# TrinketBlinkM0K.net
KiCad netlist of a schematic drawn in EAGLE
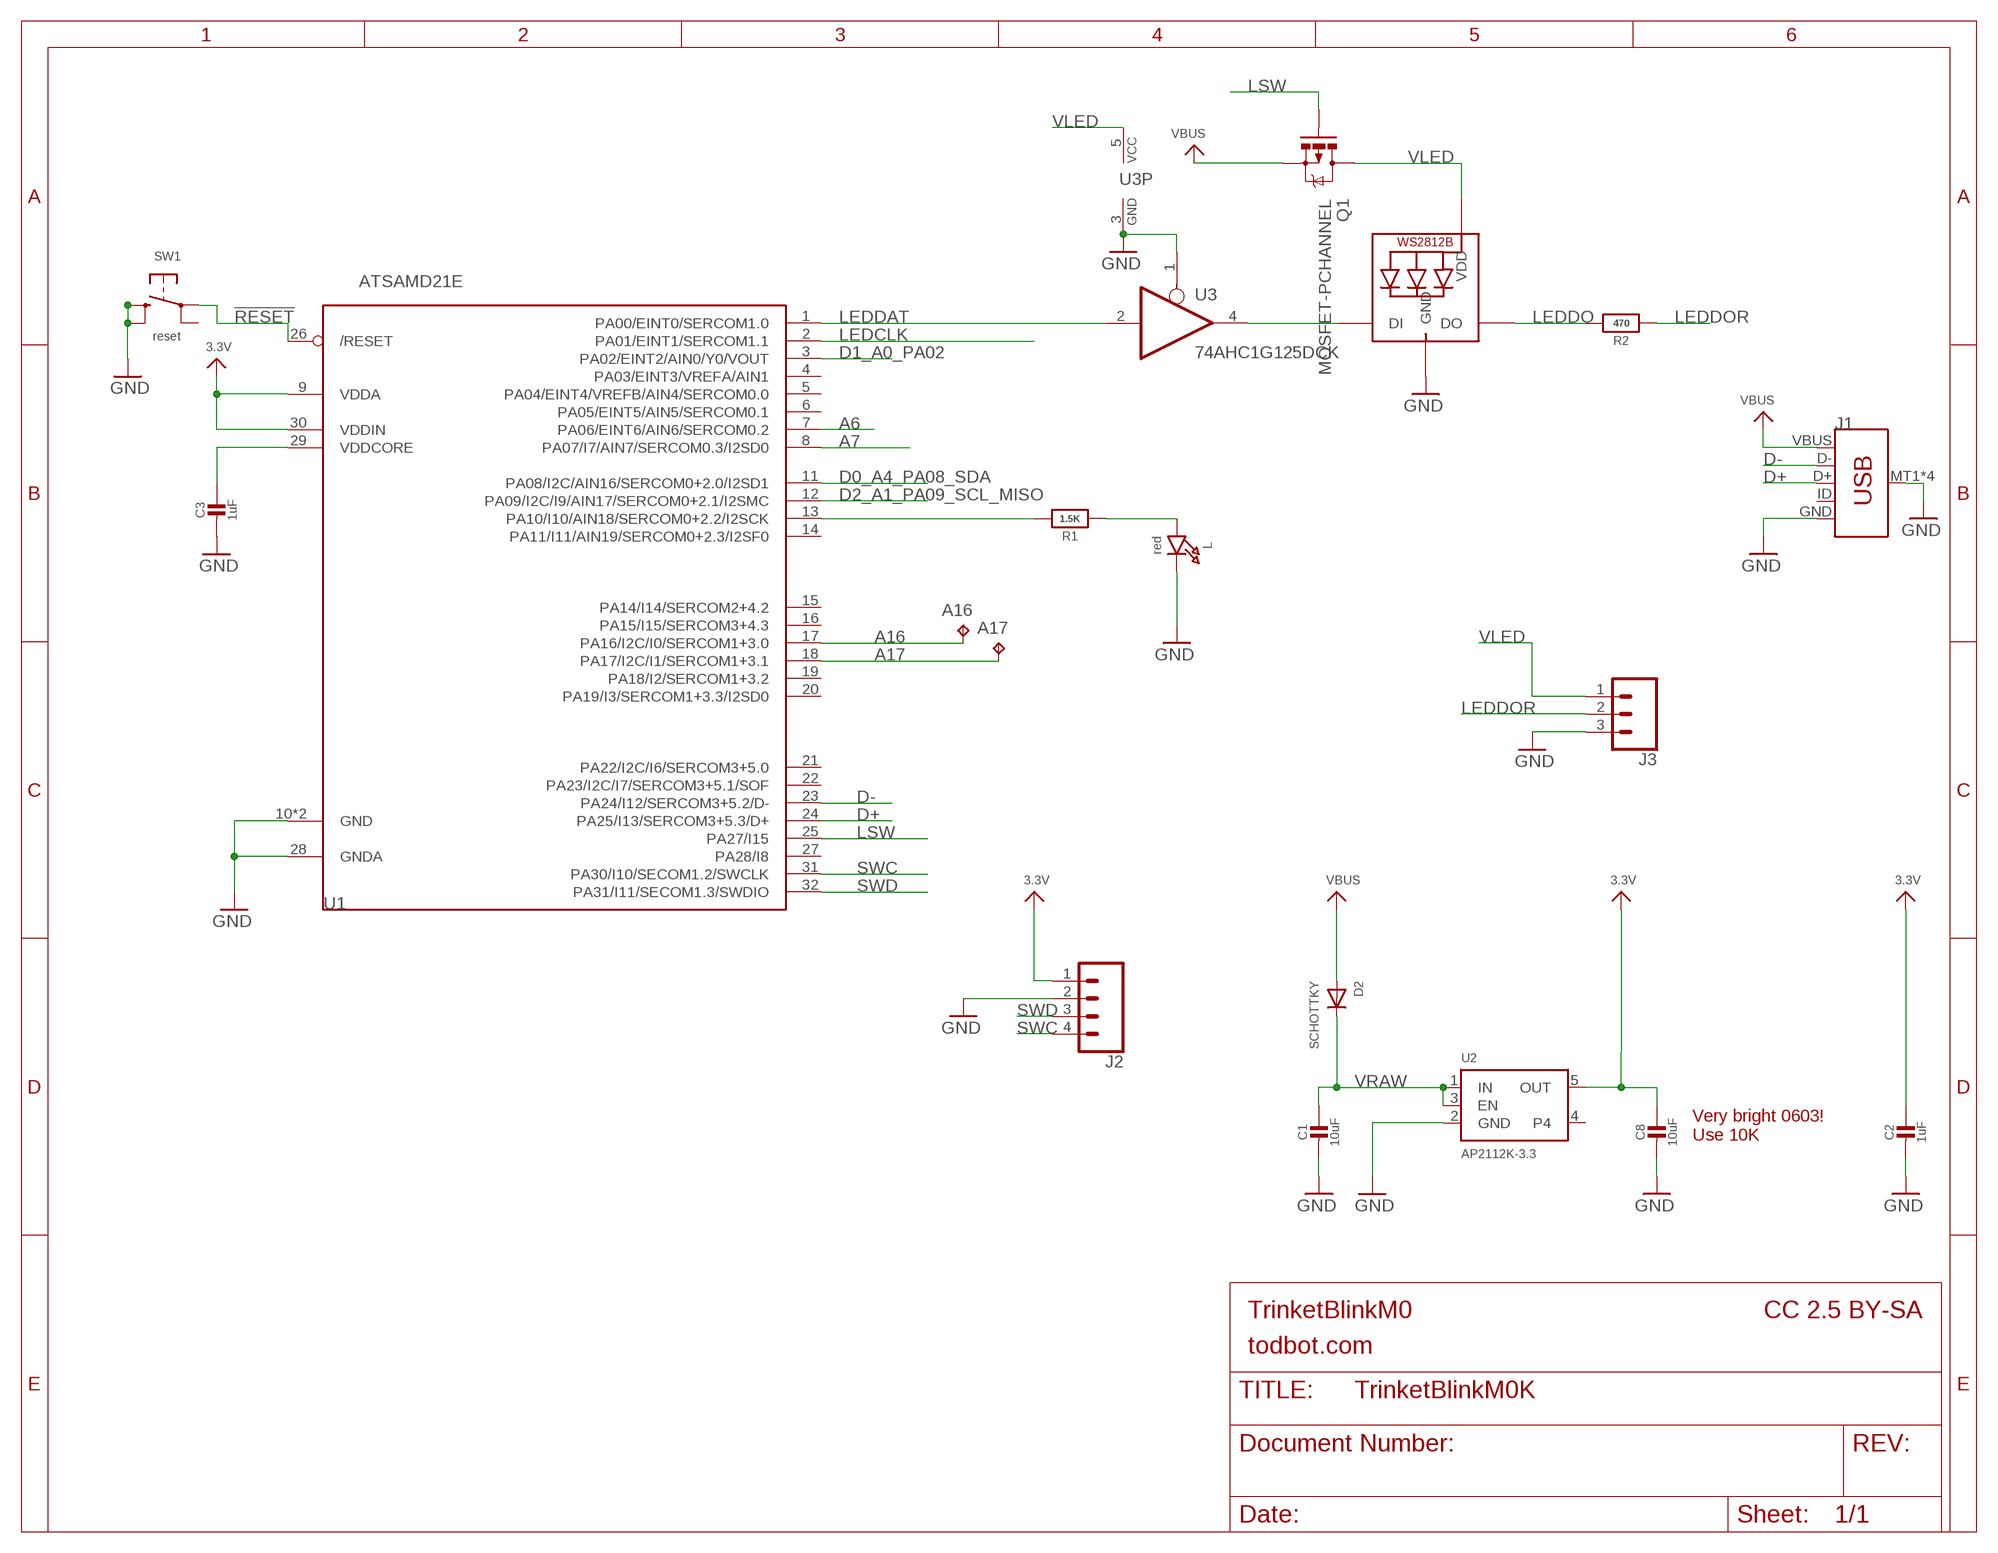
[diagram p0: schematic, sheet 1]

(export (version "E")
  (design (tool "Eeschema 10.0.6"))
  (components
    (comp (ref "A16")
      (value "TPB1,27")
      (footprint "eagle-import:B1,27")
      (libsource (lib "eagle-import") (part "TPB1,27"))
    )
    (comp (ref "A17")
      (value "TPB1,27")
      (footprint "eagle-import:B1,27")
      (libsource (lib "eagle-import") (part "TPB1,27"))
    )
    (comp (ref "C1")
      (value "10uF")
      (footprint "eagle-import:0805-NO")
      (libsource (lib "eagle-import") (part "CAP_CERAMIC0805-NOOUTLINE"))
    )
    (comp (ref "C2")
      (value "1uF")
      (footprint "eagle-import:0603-NO")
      (libsource (lib "eagle-import") (part "CAP_CERAMIC0603_NO"))
    )
    (comp (ref "C3")
      (value "1uF")
      (footprint "eagle-import:0603-NO")
      (libsource (lib "eagle-import") (part "CAP_CERAMIC0603_NO"))
    )
    (comp (ref "C8")
      (value "10uF")
      (footprint "eagle-import:0805-NO")
      (libsource (lib "eagle-import") (part "CAP_CERAMIC0805-NOOUTLINE"))
    )
    (comp (ref "D2")
      (value "SCHOTTKY")
      (footprint "eagle-import:SOD-123FL")
      (libsource (lib "eagle-import") (part "DIODE_SOD-123FL"))
    )
    (comp (ref "J1")
      (value "USB_MICRO-B_SMT")
      (footprint "eagle-import:USB-MICROB")
      (libsource (lib "eagle-import") (part "USB_MICRO-B_SMT"))
    )
    (comp (ref "J2")
      (value "CONN_04")
      (footprint "eagle-import:1X04")
      (libsource (lib "eagle-import") (part "CONN_04"))
    )
    (comp (ref "J3")
      (value "CONN_03")
      (footprint "eagle-import:1X03")
      (libsource (lib "eagle-import") (part "CONN_03"))
    )
    (comp (ref "L")
      (value "red")
      (footprint "eagle-import:CHIPLED_0603_NOOUTLINE")
      (libsource (lib "eagle-import") (part "LED0603_NOOUTLINE"))
    )
    (comp (ref "LED1")
      (value "WS2812B_5050N")
      (footprint "eagle-import:WS2812B-NARROW")
      (libsource (lib "eagle-import") (part "WS2812B_5050N"))
    )
    (comp (ref "Q1")
      (value "MOSFET-PCHANNEL")
      (footprint "eagle-import:SOT23-3")
      (libsource (lib "eagle-import") (part "MOSFET-PCHANNEL"))
    )
    (comp (ref "R1")
      (value "1.5K")
      (footprint "eagle-import:0603-NO")
      (libsource (lib "eagle-import") (part "RESISTOR_0603_NOOUT"))
    )
    (comp (ref "R2")
      (value "470")
      (footprint "eagle-import:0603-NO")
      (libsource (lib "eagle-import") (part "RESISTOR_0603_NOOUT"))
    )
    (comp (ref "SW1")
      (value "reset")
      (footprint "eagle-import:BTN_KMR2_4.6X2.8")
      (libsource (lib "eagle-import") (part "SWITCH_TACT_SMT4.6X2.8"))
    )
    (comp (ref "U1")
      (value "ATSAMD21E")
      (footprint "eagle-import:QFN32_5MM")
      (libsource (lib "eagle-import") (part "ATSAMD21E"))
    )
    (comp (ref "U2")
      (value "AP2112K-3.3")
      (footprint "eagle-import:SOT23-5")
      (libsource (lib "eagle-import") (part "VREG_SOT23-5"))
    )
    (comp (ref "U3")
      (value "74AHC1G125DCK")
      (footprint "eagle-import:SC70-5")
      (libsource (lib "eagle-import") (part "741G125DCKAHC"))
    )
  )
  (nets
    (net (code "1") (name "/A6") (class "Default")
      (node (ref "U1") (pin "7") (pinfunction "PA06/EINT6/AIN6/SERCOM0.2_7") (pintype "bidirectional"))
    )
    (net (code "2") (name "/A7") (class "Default")
      (node (ref "U1") (pin "8") (pinfunction "PA07/I7/AIN7/SERCOM0.3/I2SD0_8") (pintype "bidirectional"))
    )
    (net (code "3") (name "/A16") (class "Default")
      (node (ref "A16") (pin "TP") (pinfunction "TP_TP") (pintype "input"))
      (node (ref "U1") (pin "17") (pinfunction "PA16/I2C/I0/SERCOM1+3.0_17") (pintype "bidirectional"))
    )
    (net (code "4") (name "/A17") (class "Default")
      (node (ref "A17") (pin "TP") (pinfunction "TP_TP") (pintype "input"))
      (node (ref "U1") (pin "18") (pinfunction "PA17/I2C/I1/SERCOM1+3.1_18") (pintype "bidirectional"))
    )
    (net (code "5") (name "/D+") (class "Default")
      (node (ref "J1") (pin "D+") (pinfunction "D+_D+") (pintype "bidirectional"))
      (node (ref "U1") (pin "24") (pinfunction "PA25/I13/SERCOM3+5.3/D+_24") (pintype "bidirectional"))
    )
    (net (code "6") (name "/D-") (class "Default")
      (node (ref "J1") (pin "D-") (pinfunction "D-_D-") (pintype "bidirectional"))
      (node (ref "U1") (pin "23") (pinfunction "PA24/I12/SERCOM3+5.2/D-_23") (pintype "bidirectional"))
    )
    (net (code "7") (name "/D0_A4_PA08_SDA") (class "Default")
      (node (ref "U1") (pin "11") (pinfunction "PA08/I2C/AIN16/SERCOM0+2.0/I2SD1_11") (pintype "bidirectional"))
    )
    (net (code "8") (name "/D1_A0_PA02") (class "Default")
      (node (ref "U1") (pin "3") (pinfunction "PA02/EINT2/AIN0/Y0/VOUT_3") (pintype "bidirectional"))
    )
    (net (code "9") (name "/D2_A1_PA09_SCL_MISO") (class "Default")
      (node (ref "U1") (pin "12") (pinfunction "PA09/I2C/I9/AIN17/SERCOM0+2.1/I2SMC_12") (pintype "bidirectional"))
    )
    (net (code "10") (name "/LEDCLK") (class "Default")
      (node (ref "U1") (pin "2") (pinfunction "PA01/EINT1/SERCOM1.1_2") (pintype "bidirectional"))
    )
    (net (code "11") (name "/LEDDAT") (class "Default")
      (node (ref "U1") (pin "1") (pinfunction "PA00/EINT0/SERCOM1.0_1") (pintype "bidirectional"))
      (node (ref "U3") (pin "2") (pinfunction "I_2") (pintype "input"))
    )
    (net (code "12") (name "/LEDDO") (class "Default")
      (node (ref "LED1") (pin "2-DOUT") (pinfunction "DO_2-DOUT") (pintype "output"))
      (node (ref "R2") (pin "2") (pinfunction "2_2") (pintype "passive"))
    )
    (net (code "13") (name "/LEDDOR") (class "Default")
      (node (ref "J3") (pin "2") (pinfunction "2_2") (pintype "passive"))
      (node (ref "R2") (pin "1") (pinfunction "1_1") (pintype "passive"))
    )
    (net (code "14") (name "/LSW") (class "Default")
      (node (ref "Q1") (pin "1") (pinfunction "G_1") (pintype "passive"))
      (node (ref "U1") (pin "25") (pinfunction "PA27/I15_25") (pintype "bidirectional"))
    )
    (net (code "15") (name "/SWC") (class "Default")
      (node (ref "J2") (pin "4") (pinfunction "4_4") (pintype "passive"))
      (node (ref "U1") (pin "31") (pinfunction "PA30/I10/SECOM1.2/SWCLK_31") (pintype "bidirectional"))
    )
    (net (code "16") (name "/SWD") (class "Default")
      (node (ref "J2") (pin "3") (pinfunction "3_3") (pintype "passive"))
      (node (ref "U1") (pin "32") (pinfunction "PA31/I11/SECOM1.3/SWDIO_32") (pintype "bidirectional"))
    )
    (net (code "17") (name "/VLED") (class "Default")
      (node (ref "J3") (pin "1") (pinfunction "1_1") (pintype "passive"))
      (node (ref "LED1") (pin "1-VDD") (pinfunction "VDD_1-VDD") (pintype "power_in"))
      (node (ref "Q1") (pin "3") (pinfunction "D_3") (pintype "passive"))
      (node (ref "U3") (pin "5") (pinfunction "VCC_5") (pintype "power_in"))
    )
    (net (code "18") (name "/VRAW") (class "Default")
      (node (ref "C1") (pin "1") (pinfunction "1_1") (pintype "passive"))
      (node (ref "D2") (pin "C") (pinfunction "C_C") (pintype "passive"))
      (node (ref "U2") (pin "1") (pinfunction "IN_1") (pintype "power_in"))
      (node (ref "U2") (pin "3") (pinfunction "EN_3") (pintype "input"))
    )
    (net (code "19") (name "/~{RESET}") (class "Default")
      (node (ref "SW1") (pin "A") (pinfunction "P_A") (pintype "passive"))
      (node (ref "U1") (pin "26") (pinfunction "/RESET_26") (pintype "bidirectional"))
    )
    (net (code "20") (name "3.3V") (class "Default")
      (node (ref "C2") (pin "1") (pinfunction "1_1") (pintype "passive"))
      (node (ref "C8") (pin "1") (pinfunction "1_1") (pintype "passive"))
      (node (ref "J2") (pin "1") (pinfunction "1_1") (pintype "passive"))
      (node (ref "U1") (pin "30") (pinfunction "VDDIN_30") (pintype "power_in"))
      (node (ref "U1") (pin "9") (pinfunction "VDDA_9") (pintype "power_in"))
      (node (ref "U2") (pin "5") (pinfunction "OUT_5") (pintype "power_in"))
    )
    (net (code "21") (name "GND") (class "Default")
      (node (ref "C1") (pin "2") (pinfunction "2_2") (pintype "passive"))
      (node (ref "C2") (pin "2") (pinfunction "2_2") (pintype "passive"))
      (node (ref "C3") (pin "2") (pinfunction "2_2") (pintype "passive"))
      (node (ref "C8") (pin "2") (pinfunction "2_2") (pintype "passive"))
      (node (ref "J1") (pin "GND") (pinfunction "GND_GND") (pintype "power_in"))
      (node (ref "J1") (pin "MT1") (pinfunction "SHIELD_MT1") (pintype "bidirectional"))
      (node (ref "J1") (pin "MT2") (pinfunction "SHIELD_MT2") (pintype "bidirectional"))
      (node (ref "J1") (pin "P$1") (pinfunction "SHIELD_P$1") (pintype "bidirectional"))
      (node (ref "J1") (pin "P$2") (pinfunction "SHIELD_P$2") (pintype "bidirectional"))
      (node (ref "J2") (pin "2") (pinfunction "2_2") (pintype "passive"))
      (node (ref "J3") (pin "3") (pinfunction "3_3") (pintype "passive"))
      (node (ref "L") (pin "C") (pinfunction "C_C") (pintype "passive"))
      (node (ref "LED1") (pin "3-GND") (pinfunction "GND_3-GND") (pintype "power_in"))
      (node (ref "SW1") (pin "B") (pinfunction "S_B") (pintype "passive"))
      (node (ref "SW1") (pin "B'") (pinfunction "S1_B'") (pintype "passive"))
      (node (ref "U1") (pin "10") (pinfunction "GND_10") (pintype "power_in"))
      (node (ref "U1") (pin "28") (pinfunction "GNDA_28") (pintype "power_in"))
      (node (ref "U1") (pin "33") (pinfunction "GND_33") (pintype "power_in"))
      (node (ref "U2") (pin "2") (pinfunction "GND_2") (pintype "power_in"))
      (node (ref "U3") (pin "1") (pinfunction "OE_1") (pintype "input"))
      (node (ref "U3") (pin "3") (pinfunction "GND_3") (pintype "power_in"))
    )
    (net (code "22") (name "Net-(L-PadA)") (class "Default")
      (node (ref "L") (pin "A") (pinfunction "A_A") (pintype "passive"))
      (node (ref "R1") (pin "1") (pinfunction "1_1") (pintype "passive"))
    )
    (net (code "23") (name "Net-(LED1-DI)") (class "Default")
      (node (ref "LED1") (pin "4-DIN") (pinfunction "DI_4-DIN") (pintype "input"))
      (node (ref "U3") (pin "4") (pinfunction "O_4") (pintype "tri_state"))
    )
    (net (code "24") (name "Net-(U1-PA10{slash}I10{slash}AIN18{slash}SERCOM0+2.2{slash}I2SCK)") (class "Default")
      (node (ref "R1") (pin "2") (pinfunction "2_2") (pintype "passive"))
      (node (ref "U1") (pin "13") (pinfunction "PA10/I10/AIN18/SERCOM0+2.2/I2SCK_13") (pintype "bidirectional"))
    )
    (net (code "25") (name "Net-(U1-VDDCORE)") (class "Default")
      (node (ref "C3") (pin "1") (pinfunction "1_1") (pintype "passive"))
      (node (ref "U1") (pin "29") (pinfunction "VDDCORE_29") (pintype "power_in"))
    )
    (net (code "26") (name "VBUS") (class "Default")
      (node (ref "D2") (pin "A") (pinfunction "A_A") (pintype "passive"))
      (node (ref "J1") (pin "VBUS") (pinfunction "VBUS_VBUS") (pintype "power_in"))
      (node (ref "Q1") (pin "2") (pinfunction "S_2") (pintype "passive"))
    )
    (net (code "27") (name "unconnected-(J1-PadID)") (class "Default")
      (node (ref "J1") (pin "ID") (pinfunction "ID_ID") (pintype "bidirectional"))
    )
    (net (code "28") (name "unconnected-(SW1-P1-PadA')") (class "Default")
      (node (ref "SW1") (pin "A'") (pinfunction "P1_A'") (pintype "passive"))
    )
    (net (code "29") (name "unconnected-(U1-PA03{slash}EINT3{slash}VREFA{slash}AIN1-Pad4)") (class "Default")
      (node (ref "U1") (pin "4") (pinfunction "PA03/EINT3/VREFA/AIN1_4") (pintype "bidirectional"))
    )
    (net (code "30") (name "unconnected-(U1-PA04{slash}EINT4{slash}VREFB{slash}AIN4{slash}SERCOM0.0-Pad5)") (class "Default")
      (node (ref "U1") (pin "5") (pinfunction "PA04/EINT4/VREFB/AIN4/SERCOM0.0_5") (pintype "bidirectional"))
    )
    (net (code "31") (name "unconnected-(U1-PA05{slash}EINT5{slash}AIN5{slash}SERCOM0.1-Pad6)") (class "Default")
      (node (ref "U1") (pin "6") (pinfunction "PA05/EINT5/AIN5/SERCOM0.1_6") (pintype "bidirectional"))
    )
    (net (code "32") (name "unconnected-(U1-PA11{slash}I11{slash}AIN19{slash}SERCOM0+2.3{slash}I2SF0-Pad14)") (class "Default")
      (node (ref "U1") (pin "14") (pinfunction "PA11/I11/AIN19/SERCOM0+2.3/I2SF0_14") (pintype "bidirectional"))
    )
    (net (code "33") (name "unconnected-(U1-PA14{slash}I14{slash}SERCOM2+4.2-Pad15)") (class "Default")
      (node (ref "U1") (pin "15") (pinfunction "PA14/I14/SERCOM2+4.2_15") (pintype "bidirectional"))
    )
    (net (code "34") (name "unconnected-(U1-PA15{slash}I15{slash}SERCOM3+4.3-Pad16)") (class "Default")
      (node (ref "U1") (pin "16") (pinfunction "PA15/I15/SERCOM3+4.3_16") (pintype "bidirectional"))
    )
    (net (code "35") (name "unconnected-(U1-PA18{slash}I2{slash}SERCOM1+3.2-Pad19)") (class "Default")
      (node (ref "U1") (pin "19") (pinfunction "PA18/I2/SERCOM1+3.2_19") (pintype "bidirectional"))
    )
    (net (code "36") (name "unconnected-(U1-PA19{slash}I3{slash}SERCOM1+3.3{slash}I2SD0-Pad20)") (class "Default")
      (node (ref "U1") (pin "20") (pinfunction "PA19/I3/SERCOM1+3.3/I2SD0_20") (pintype "bidirectional"))
    )
    (net (code "37") (name "unconnected-(U1-PA22{slash}I2C{slash}I6{slash}SERCOM3+5.0-Pad21)") (class "Default")
      (node (ref "U1") (pin "21") (pinfunction "PA22/I2C/I6/SERCOM3+5.0_21") (pintype "bidirectional"))
    )
    (net (code "38") (name "unconnected-(U1-PA23{slash}I2C{slash}I7{slash}SERCOM3+5.1{slash}SOF-Pad22)") (class "Default")
      (node (ref "U1") (pin "22") (pinfunction "PA23/I2C/I7/SERCOM3+5.1/SOF_22") (pintype "bidirectional"))
    )
    (net (code "39") (name "unconnected-(U1-PA28{slash}I8-Pad27)") (class "Default")
      (node (ref "U1") (pin "27") (pinfunction "PA28/I8_27") (pintype "bidirectional"))
    )
    (net (code "40") (name "unconnected-(U2-P4-Pad4)") (class "Default")
      (node (ref "U2") (pin "4") (pinfunction "P4_4") (pintype "bidirectional"))
    )
  )
)
